# 3Sens_lowPass.net
KiCad netlist of a schematic drawn in EAGLE
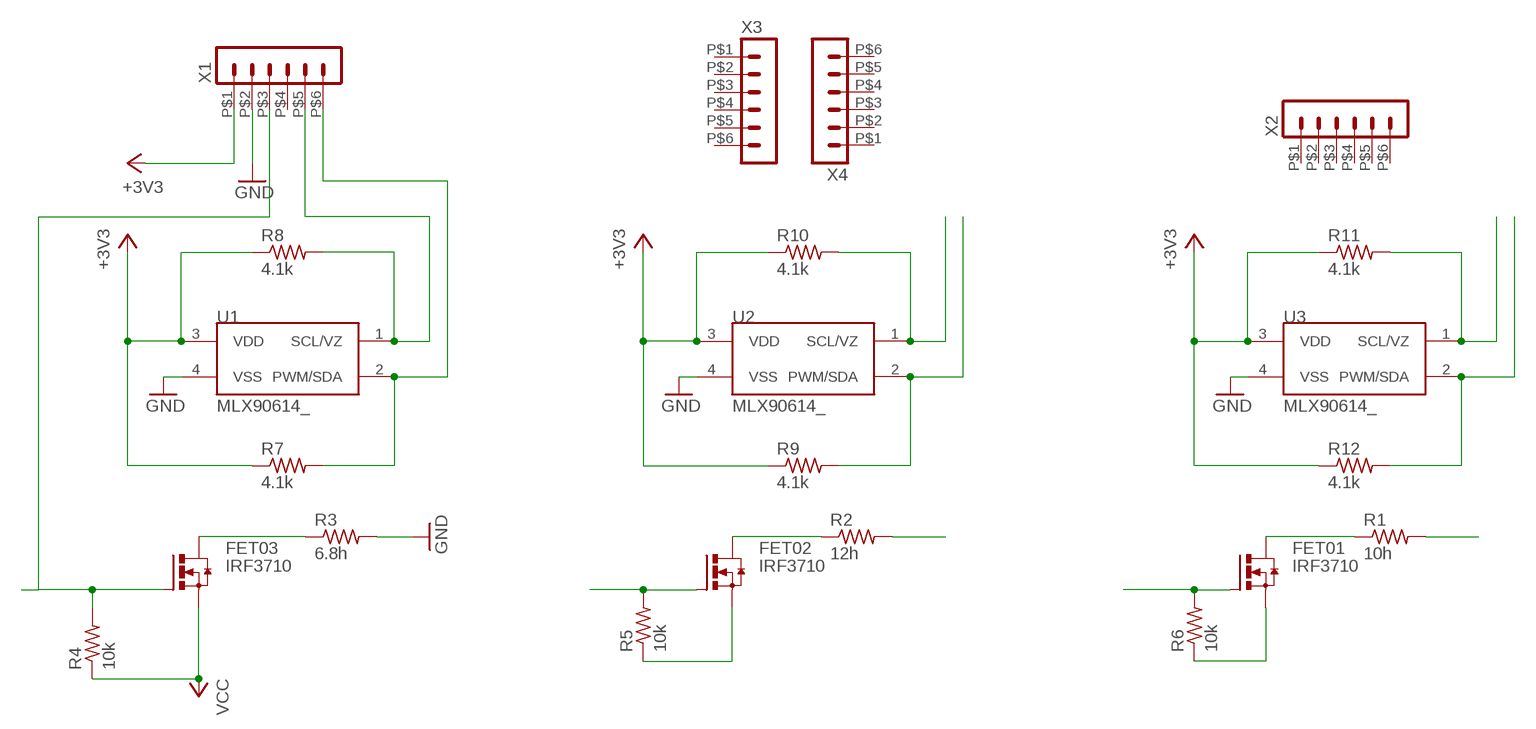
[diagram p0: schematic, sheet 1]

(export (version "E")
  (design (tool "Eeschema 10.0.6"))
  (components
    (comp (ref "FET01")
      (value "IRF3710")
      (footprint "eagle-import:TO220AH")
      (libsource (lib "eagle-import") (part "IRF3704"))
    )
    (comp (ref "FET02")
      (value "IRF3710")
      (footprint "eagle-import:TO220AH")
      (libsource (lib "eagle-import") (part "IRF3704"))
    )
    (comp (ref "FET03")
      (value "IRF3710")
      (footprint "eagle-import:TO220AH")
      (libsource (lib "eagle-import") (part "IRF3704"))
    )
    (comp (ref "R1")
      (value "10h")
      (footprint "eagle-import:0204V")
      (libsource (lib "eagle-import") (part "R-US_0204/2V"))
    )
    (comp (ref "R2")
      (value "12h")
      (footprint "eagle-import:0204V")
      (libsource (lib "eagle-import") (part "R-US_0204/2V"))
    )
    (comp (ref "R3")
      (value "6.8h")
      (footprint "eagle-import:0204V")
      (libsource (lib "eagle-import") (part "R-US_0204/2V"))
    )
    (comp (ref "R4")
      (value "10k")
      (footprint "eagle-import:0204V")
      (libsource (lib "eagle-import") (part "R-US_0204/2V"))
    )
    (comp (ref "R5")
      (value "10k")
      (footprint "eagle-import:0204V")
      (libsource (lib "eagle-import") (part "R-US_0204/2V"))
    )
    (comp (ref "R6")
      (value "10k")
      (footprint "eagle-import:0204V")
      (libsource (lib "eagle-import") (part "R-US_0204/2V"))
    )
    (comp (ref "R7")
      (value "4.1k")
      (footprint "eagle-import:0204V")
      (libsource (lib "eagle-import") (part "R-US_0204/2V"))
    )
    (comp (ref "R8")
      (value "4.1k")
      (footprint "eagle-import:0204V")
      (libsource (lib "eagle-import") (part "R-US_0204/2V"))
    )
    (comp (ref "R9")
      (value "4.1k")
      (footprint "eagle-import:0204V")
      (libsource (lib "eagle-import") (part "R-US_0204/2V"))
    )
    (comp (ref "R10")
      (value "4.1k")
      (footprint "eagle-import:0204V")
      (libsource (lib "eagle-import") (part "R-US_0204/2V"))
    )
    (comp (ref "R11")
      (value "4.1k")
      (footprint "eagle-import:0204V")
      (libsource (lib "eagle-import") (part "R-US_0204/2V"))
    )
    (comp (ref "R12")
      (value "4.1k")
      (footprint "eagle-import:0204V")
      (libsource (lib "eagle-import") (part "R-US_0204/2V"))
    )
    (comp (ref "U1")
      (value "MLX90614_")
      (footprint "eagle-import:TO-39")
      (libsource (lib "eagle-import") (part "MLX90614_"))
    )
    (comp (ref "U2")
      (value "MLX90614_")
      (footprint "eagle-import:TO-39")
      (libsource (lib "eagle-import") (part "MLX90614_"))
    )
    (comp (ref "U3")
      (value "MLX90614_")
      (footprint "eagle-import:TO-39")
      (libsource (lib "eagle-import") (part "MLX90614_"))
    )
    (comp (ref "X1")
      (value "HEADER_POS6_43045-0600")
      (footprint "eagle-import:43045-0600")
      (libsource (lib "eagle-import") (part "HEADER_POS6_?43045-0600"))
    )
    (comp (ref "X2")
      (value "HEADER_POS6_43045-0600")
      (footprint "eagle-import:43045-0600")
      (libsource (lib "eagle-import") (part "HEADER_POS6_?43045-0600"))
    )
    (comp (ref "X3")
      (value "HEADER_POS6_43650-0600")
      (footprint "eagle-import:43650-0600")
      (libsource (lib "eagle-import") (part "HEADER_POS6_?43650-0600"))
    )
    (comp (ref "X4")
      (value "HEADER_POS6_43650-0600")
      (footprint "eagle-import:43650-0600")
      (libsource (lib "eagle-import") (part "HEADER_POS6_?43650-0600"))
    )
  )
  (nets
    (net (code "1") (name "+3V3") (class "Default")
      (node (ref "R10") (pin "1") (pinfunction "1_1") (pintype "passive"))
      (node (ref "R11") (pin "1") (pinfunction "1_1") (pintype "passive"))
      (node (ref "R12") (pin "1") (pinfunction "1_1") (pintype "passive"))
      (node (ref "R7") (pin "1") (pinfunction "1_1") (pintype "passive"))
      (node (ref "R8") (pin "1") (pinfunction "1_1") (pintype "passive"))
      (node (ref "R9") (pin "1") (pinfunction "1_1") (pintype "passive"))
      (node (ref "U1") (pin "3") (pinfunction "VDD_3") (pintype "bidirectional"))
      (node (ref "U2") (pin "3") (pinfunction "VDD_3") (pintype "bidirectional"))
      (node (ref "U3") (pin "3") (pinfunction "VDD_3") (pintype "bidirectional"))
      (node (ref "X1") (pin "P$1") (pinfunction "1_P$1") (pintype "passive"))
    )
    (net (code "2") (name "GND") (class "Default")
      (node (ref "R3") (pin "2") (pinfunction "2_2") (pintype "passive"))
      (node (ref "U1") (pin "4") (pinfunction "VSS_4") (pintype "bidirectional"))
      (node (ref "U2") (pin "4") (pinfunction "VSS_4") (pintype "bidirectional"))
      (node (ref "U3") (pin "4") (pinfunction "VSS_4") (pintype "bidirectional"))
      (node (ref "X1") (pin "P$2") (pinfunction "2_P$2") (pintype "passive"))
    )
    (net (code "3") (name "Net-(FET01-D)") (class "Default")
      (node (ref "FET01") (pin "C") (pinfunction "D_C") (pintype "passive"))
      (node (ref "R1") (pin "1") (pinfunction "1_1") (pintype "passive"))
    )
    (net (code "4") (name "Net-(FET01-G)") (class "Default")
      (node (ref "FET01") (pin "B") (pinfunction "G_B") (pintype "passive"))
      (node (ref "R6") (pin "2") (pinfunction "2_2") (pintype "passive"))
    )
    (net (code "5") (name "Net-(FET01-S)") (class "Default")
      (node (ref "FET01") (pin "E") (pinfunction "S_E") (pintype "passive"))
      (node (ref "R6") (pin "1") (pinfunction "1_1") (pintype "passive"))
    )
    (net (code "6") (name "Net-(FET02-D)") (class "Default")
      (node (ref "FET02") (pin "C") (pinfunction "D_C") (pintype "passive"))
      (node (ref "R2") (pin "1") (pinfunction "1_1") (pintype "passive"))
    )
    (net (code "7") (name "Net-(FET02-G)") (class "Default")
      (node (ref "FET02") (pin "B") (pinfunction "G_B") (pintype "passive"))
      (node (ref "R5") (pin "2") (pinfunction "2_2") (pintype "passive"))
    )
    (net (code "8") (name "Net-(FET02-S)") (class "Default")
      (node (ref "FET02") (pin "E") (pinfunction "S_E") (pintype "passive"))
      (node (ref "R5") (pin "1") (pinfunction "1_1") (pintype "passive"))
    )
    (net (code "9") (name "Net-(FET03-D)") (class "Default")
      (node (ref "FET03") (pin "C") (pinfunction "D_C") (pintype "passive"))
      (node (ref "R3") (pin "1") (pinfunction "1_1") (pintype "passive"))
    )
    (net (code "10") (name "Net-(FET03-G)") (class "Default")
      (node (ref "FET03") (pin "B") (pinfunction "G_B") (pintype "passive"))
      (node (ref "R4") (pin "2") (pinfunction "2_2") (pintype "passive"))
      (node (ref "X1") (pin "P$3") (pinfunction "3_P$3") (pintype "passive"))
    )
    (net (code "11") (name "Net-(U1-PWM{slash}SDA)") (class "Default")
      (node (ref "R7") (pin "2") (pinfunction "2_2") (pintype "passive"))
      (node (ref "U1") (pin "2") (pinfunction "PWM/SDA_2") (pintype "bidirectional"))
      (node (ref "X1") (pin "P$6") (pinfunction "6_P$6") (pintype "passive"))
    )
    (net (code "12") (name "Net-(U1-SCL{slash}VZ)") (class "Default")
      (node (ref "R8") (pin "2") (pinfunction "2_2") (pintype "passive"))
      (node (ref "U1") (pin "1") (pinfunction "SCL/VZ_1") (pintype "bidirectional"))
      (node (ref "X1") (pin "P$5") (pinfunction "5_P$5") (pintype "passive"))
    )
    (net (code "13") (name "Net-(U2-PWM{slash}SDA)") (class "Default")
      (node (ref "R9") (pin "2") (pinfunction "2_2") (pintype "passive"))
      (node (ref "U2") (pin "2") (pinfunction "PWM/SDA_2") (pintype "bidirectional"))
    )
    (net (code "14") (name "Net-(U2-SCL{slash}VZ)") (class "Default")
      (node (ref "R10") (pin "2") (pinfunction "2_2") (pintype "passive"))
      (node (ref "U2") (pin "1") (pinfunction "SCL/VZ_1") (pintype "bidirectional"))
    )
    (net (code "15") (name "Net-(U3-PWM{slash}SDA)") (class "Default")
      (node (ref "R12") (pin "2") (pinfunction "2_2") (pintype "passive"))
      (node (ref "U3") (pin "2") (pinfunction "PWM/SDA_2") (pintype "bidirectional"))
    )
    (net (code "16") (name "Net-(U3-SCL{slash}VZ)") (class "Default")
      (node (ref "R11") (pin "2") (pinfunction "2_2") (pintype "passive"))
      (node (ref "U3") (pin "1") (pinfunction "SCL/VZ_1") (pintype "bidirectional"))
    )
    (net (code "17") (name "VCC") (class "Default")
      (node (ref "FET03") (pin "E") (pinfunction "S_E") (pintype "passive"))
      (node (ref "R4") (pin "1") (pinfunction "1_1") (pintype "passive"))
    )
    (net (code "18") (name "unconnected-(R1-Pad2)") (class "Default")
      (node (ref "R1") (pin "2") (pinfunction "2_2") (pintype "passive"))
    )
    (net (code "19") (name "unconnected-(R2-Pad2)") (class "Default")
      (node (ref "R2") (pin "2") (pinfunction "2_2") (pintype "passive"))
    )
    (net (code "20") (name "unconnected-(X1-4-PadP$4)") (class "Default")
      (node (ref "X1") (pin "P$4") (pinfunction "4_P$4") (pintype "passive"))
    )
    (net (code "21") (name "unconnected-(X2-1-PadP$1)") (class "Default")
      (node (ref "X2") (pin "P$1") (pinfunction "1_P$1") (pintype "passive"))
    )
    (net (code "22") (name "unconnected-(X2-2-PadP$2)") (class "Default")
      (node (ref "X2") (pin "P$2") (pinfunction "2_P$2") (pintype "passive"))
    )
    (net (code "23") (name "unconnected-(X2-3-PadP$3)") (class "Default")
      (node (ref "X2") (pin "P$3") (pinfunction "3_P$3") (pintype "passive"))
    )
    (net (code "24") (name "unconnected-(X2-4-PadP$4)") (class "Default")
      (node (ref "X2") (pin "P$4") (pinfunction "4_P$4") (pintype "passive"))
    )
    (net (code "25") (name "unconnected-(X2-5-PadP$5)") (class "Default")
      (node (ref "X2") (pin "P$5") (pinfunction "5_P$5") (pintype "passive"))
    )
    (net (code "26") (name "unconnected-(X2-6-PadP$6)") (class "Default")
      (node (ref "X2") (pin "P$6") (pinfunction "6_P$6") (pintype "passive"))
    )
    (net (code "27") (name "unconnected-(X3-1-PadP$1)") (class "Default")
      (node (ref "X3") (pin "P$1") (pinfunction "1_P$1") (pintype "passive"))
    )
    (net (code "28") (name "unconnected-(X3-2-PadP$2)") (class "Default")
      (node (ref "X3") (pin "P$2") (pinfunction "2_P$2") (pintype "passive"))
    )
    (net (code "29") (name "unconnected-(X3-3-PadP$3)") (class "Default")
      (node (ref "X3") (pin "P$3") (pinfunction "3_P$3") (pintype "passive"))
    )
    (net (code "30") (name "unconnected-(X3-4-PadP$4)") (class "Default")
      (node (ref "X3") (pin "P$4") (pinfunction "4_P$4") (pintype "passive"))
    )
    (net (code "31") (name "unconnected-(X3-5-PadP$5)") (class "Default")
      (node (ref "X3") (pin "P$5") (pinfunction "5_P$5") (pintype "passive"))
    )
    (net (code "32") (name "unconnected-(X3-6-PadP$6)") (class "Default")
      (node (ref "X3") (pin "P$6") (pinfunction "6_P$6") (pintype "passive"))
    )
    (net (code "33") (name "unconnected-(X4-1-PadP$1)") (class "Default")
      (node (ref "X4") (pin "P$1") (pinfunction "1_P$1") (pintype "passive"))
    )
    (net (code "34") (name "unconnected-(X4-2-PadP$2)") (class "Default")
      (node (ref "X4") (pin "P$2") (pinfunction "2_P$2") (pintype "passive"))
    )
    (net (code "35") (name "unconnected-(X4-3-PadP$3)") (class "Default")
      (node (ref "X4") (pin "P$3") (pinfunction "3_P$3") (pintype "passive"))
    )
    (net (code "36") (name "unconnected-(X4-4-PadP$4)") (class "Default")
      (node (ref "X4") (pin "P$4") (pinfunction "4_P$4") (pintype "passive"))
    )
    (net (code "37") (name "unconnected-(X4-5-PadP$5)") (class "Default")
      (node (ref "X4") (pin "P$5") (pinfunction "5_P$5") (pintype "passive"))
    )
    (net (code "38") (name "unconnected-(X4-6-PadP$6)") (class "Default")
      (node (ref "X4") (pin "P$6") (pinfunction "6_P$6") (pintype "passive"))
    )
  )
)
